# 16_MIPI_DSI_TX.net
KiCad netlist of a schematic drawn in Altium Designer
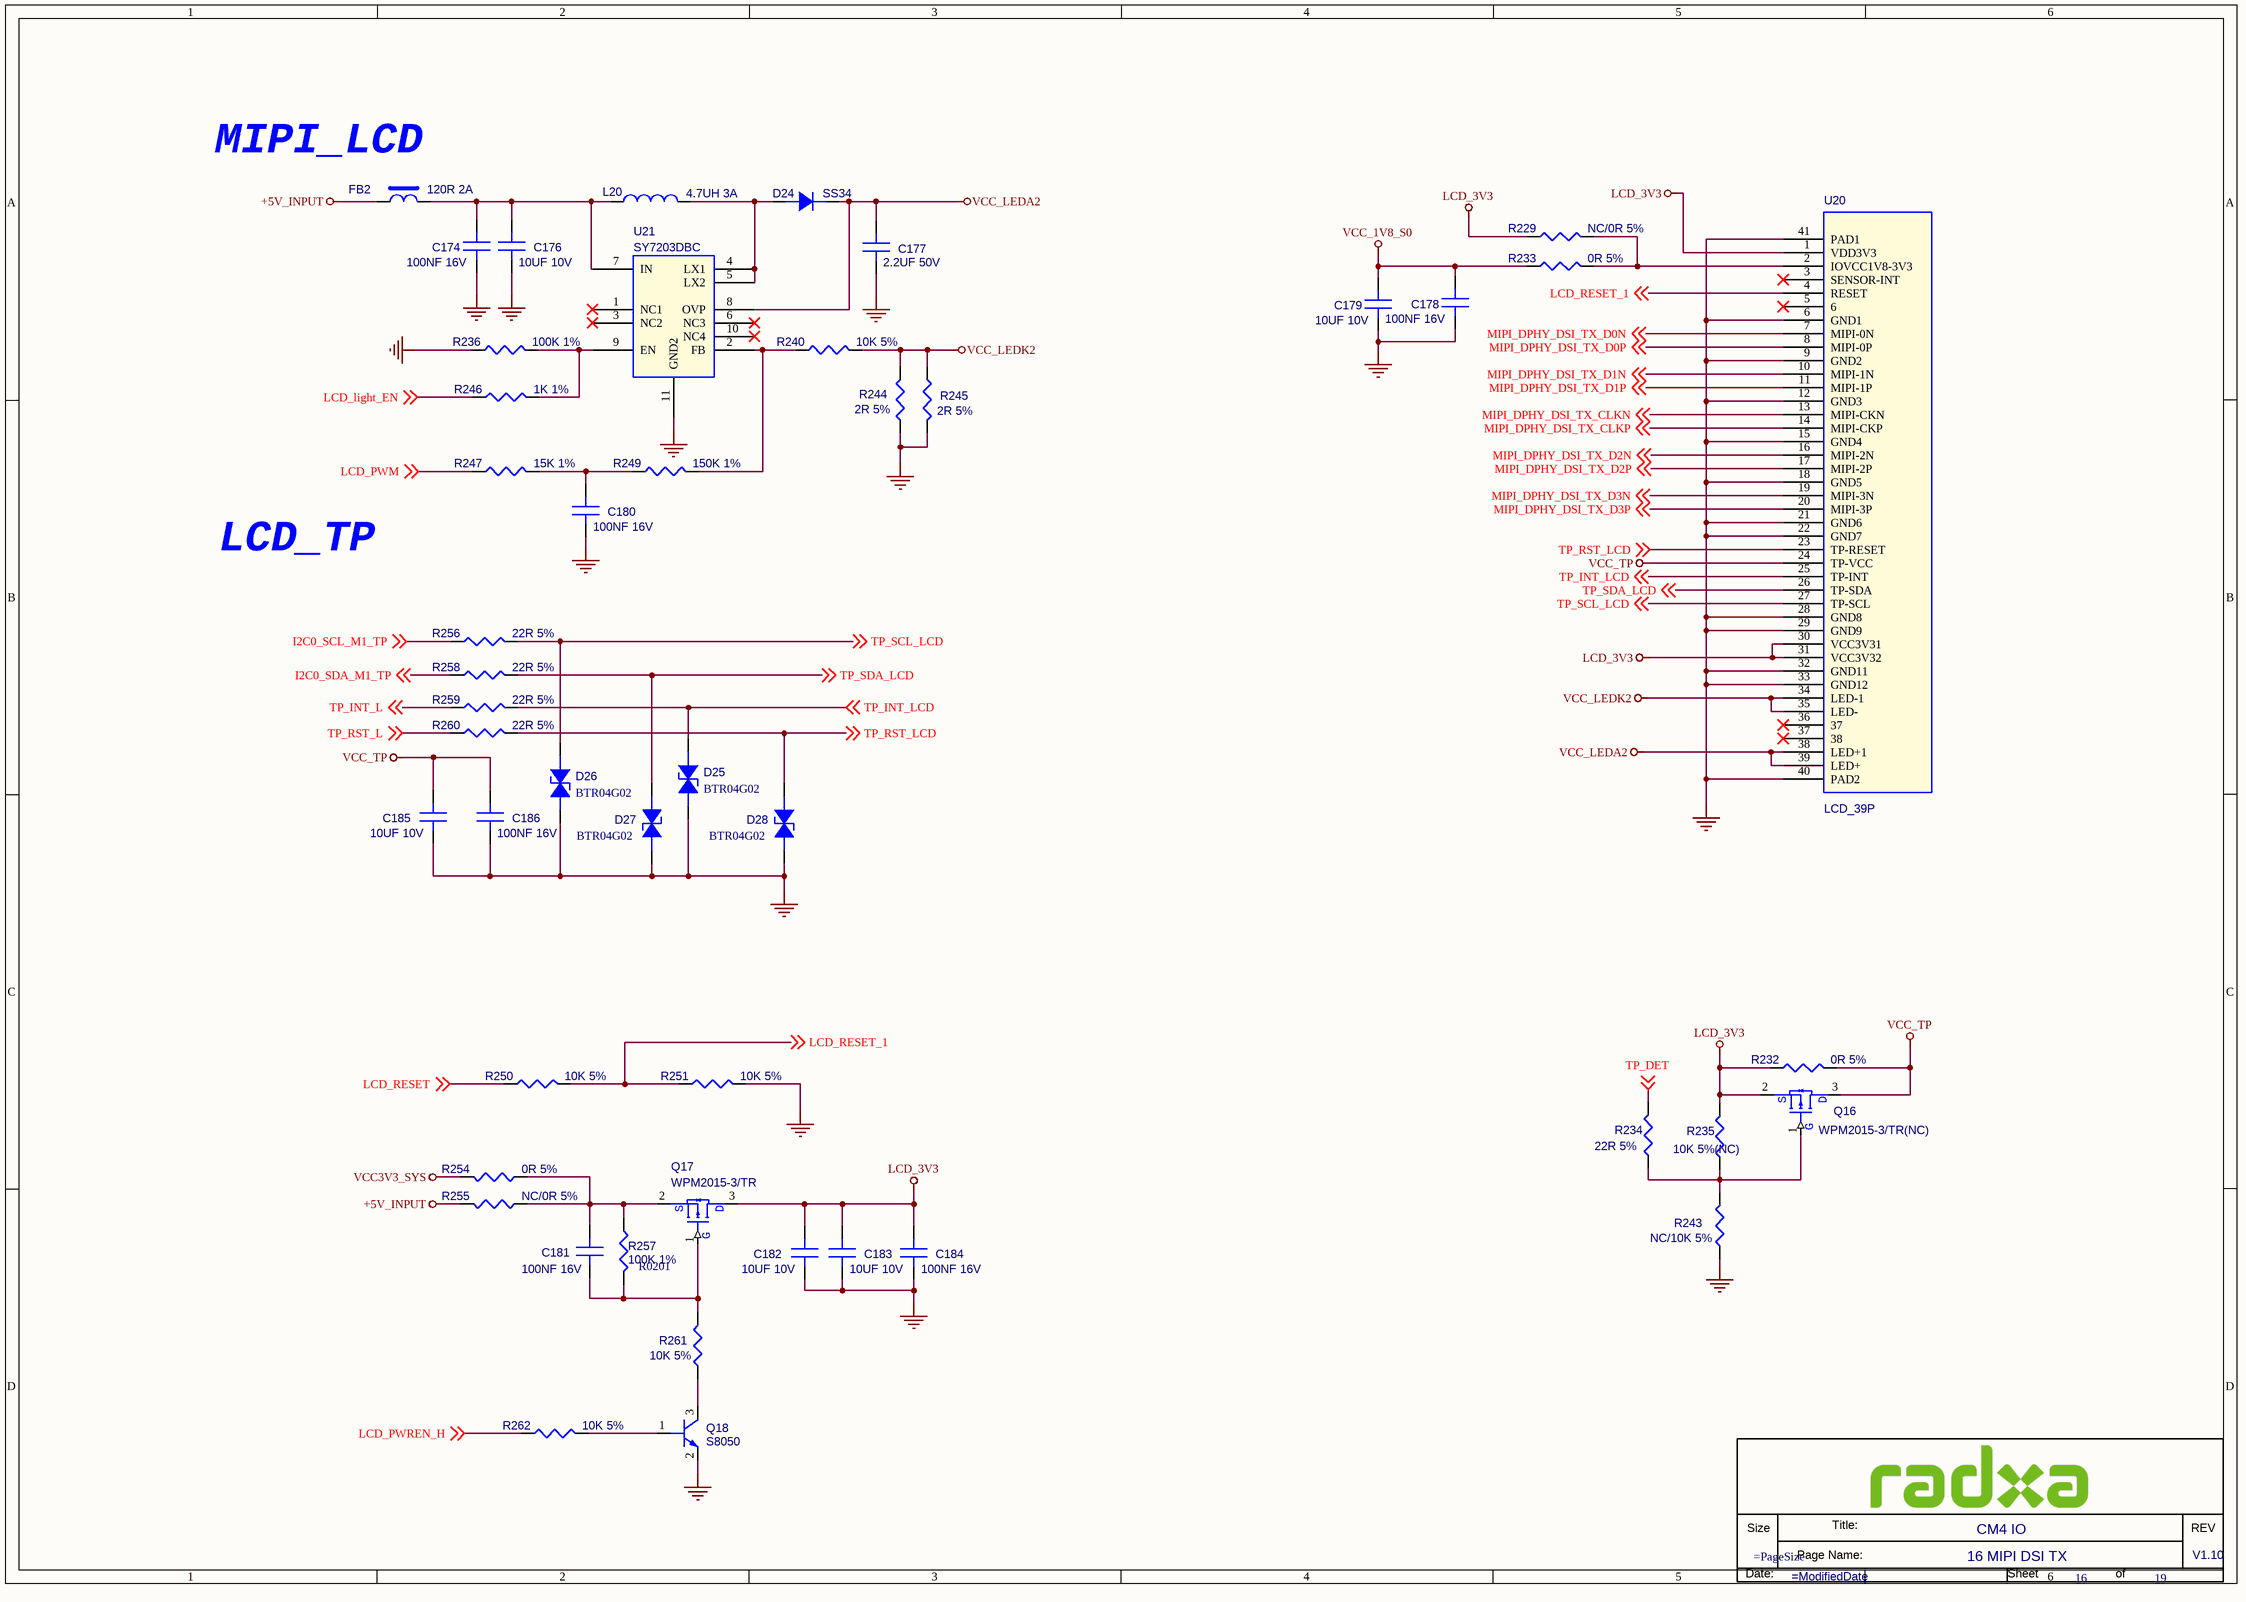
[diagram p0: 16 MIPI DSI TX.SchDoc]

(export (version "E")
  (design (tool "Eeschema 10.0.6"))
  (components
    (comp (ref "C174")
      (value "100NF 16V")
      (footprint "C0201")
      (description "SMD  0201  100NF  16V  X5R  ±20%  ROHS")
      (fields (field (name "PART NUMBER") "A1C01.00099"))
      (libsource (lib "*") (part "C"))
    )
    (comp (ref "C176")
      (value "10UF 10V")
      (footprint "C0603")
      (description "SMD  0603  10UF  10V  X5R  ±10%  ROHS")
      (fields (field (name "PART NUMBER") "A1C01.00270"))
      (libsource (lib "*") (part "C"))
    )
    (comp (ref "C177")
      (value "2.2UF 50V")
      (footprint "C0603")
      (description "SMD  0603  2.2UF  50V  X5R  ±10%  ROHS")
      (fields (field (name "PART NUMBER") "A1C01.00235"))
      (libsource (lib "*") (part "C"))
    )
    (comp (ref "C178")
      (value "100NF 16V")
      (footprint "C0201")
      (description "SMD  0201  100NF  16V  X5R  ±20%  ROHS")
      (fields (field (name "PART NUMBER") "A1C01.00099"))
      (libsource (lib "*") (part "C"))
    )
    (comp (ref "C179")
      (value "10UF 10V")
      (footprint "C0603")
      (description "SMD  0603  10UF  10V  X5R  ±10%  ROHS")
      (fields (field (name "PART NUMBER") "A1C01.00270"))
      (libsource (lib "*") (part "C"))
    )
    (comp (ref "C180")
      (value "100NF 16V")
      (footprint "C0201")
      (description "SMD  0201  100NF  16V  X5R  ±20%  ROHS")
      (fields (field (name "PART NUMBER") "A1C01.00099"))
      (libsource (lib "*") (part "C"))
    )
    (comp (ref "C181")
      (value "100NF 16V")
      (footprint "C0201")
      (description "SMD  0201  100NF  16V  X5R  ±20%  ROHS")
      (fields (field (name "PART NUMBER") "A1C01.00099"))
      (libsource (lib "*") (part "C"))
    )
    (comp (ref "C182")
      (value "10UF 10V")
      (footprint "C0603")
      (description "SMD  0603  10UF  10V  X5R  ±10%  ROHS")
      (fields (field (name "PART NUMBER") "A1C01.00270"))
      (libsource (lib "*") (part "C"))
    )
    (comp (ref "C183")
      (value "10UF 10V")
      (footprint "C0603")
      (description "SMD  0603  10UF  10V  X5R  ±10%  ROHS")
      (fields (field (name "PART NUMBER") "A1C01.00270"))
      (libsource (lib "*") (part "C"))
    )
    (comp (ref "C184")
      (value "100NF 16V")
      (footprint "C0201")
      (description "SMD  0201  100NF  16V  X5R  ±20%  ROHS")
      (fields (field (name "PART NUMBER") "A1C01.00099"))
      (libsource (lib "*") (part "C"))
    )
    (comp (ref "C185")
      (value "10UF 10V")
      (footprint "C0603")
      (description "SMD  0603  10UF  10V  X5R  ±10%  ROHS")
      (fields (field (name "PART NUMBER") "A1C01.00270"))
      (libsource (lib "*") (part "C"))
    )
    (comp (ref "C186")
      (value "100NF 16V")
      (footprint "C0201")
      (description "SMD  0201  100NF  16V  X5R  ±20%  ROHS")
      (fields (field (name "PART NUMBER") "A1C01.00099"))
      (libsource (lib "*") (part "C"))
    )
    (comp (ref "D24")
      (value "SS34")
      (footprint "DO_214AC")
      (description "SMD  编带  DO-214AC  SS34  CJ  ROHS")
      (fields (field (name "PART NUMBER") "A1D02.00052"))
      (libsource (lib "*") (part "DIODE"))
    )
    (comp (ref "D25")
      (value "BTR04G02")
      (footprint "DFN1006-2L")
      (description "SMD  编带  0402  BTR04G02  B-tron  ROHS")
      (fields (field (name "PART NUMBER") "A1D02.00002"))
      (libsource (lib "*") (part "ESD"))
    )
    (comp (ref "D26")
      (value "BTR04G02")
      (footprint "DFN1006-2L")
      (description "SMD  编带  0402  BTR04G02  B-tron  ROHS")
      (fields (field (name "PART NUMBER") "A1D02.00002"))
      (libsource (lib "*") (part "ESD"))
    )
    (comp (ref "D27")
      (value "BTR04G02")
      (footprint "DFN1006-2L")
      (description "SMD  编带  0402  BTR04G02  B-tron  ROHS")
      (fields (field (name "PART NUMBER") "A1D02.00002"))
      (libsource (lib "*") (part "ESD"))
    )
    (comp (ref "D28")
      (value "BTR04G02")
      (footprint "DFN1006-2L")
      (description "SMD  编带  0402  BTR04G02  B-tron  ROHS")
      (fields (field (name "PART NUMBER") "A1D02.00002"))
      (libsource (lib "*") (part "ESD"))
    )
    (comp (ref "FB2")
      (value "120R 2A")
      (footprint "FB0603")
      (description "SMD  0603  FB120R  2A  PZ1608U121-2R0TF  ±25%  Sunlord(顺络)  ROHS")
      (fields (field (name "PART NUMBER") "A1L09.00003"))
      (libsource (lib "*") (part "BEAD"))
    )
    (comp (ref "L20")
      (value "4.7UH 3A")
      (footprint "L_3015")
      (description "SMD  带屏蔽  3*3*1.5mm  4.7UH  3A  ±20%  RXWHJ3015-4R7MT  ROHS")
      (fields (field (name "PART NUMBER") "A1L01.00021"))
      (libsource (lib "*") (part "L"))
    )
    (comp (ref "Q16")
      (value "WPM2015-3/TR(NC)")
      (footprint "SOT_23")
      (description "SMD编带  SOT-23  WPM2015-3/TR  P沟道  ROHS")
      (fields (field (name "PART NUMBER") "A1D01.00019"))
      (libsource (lib "*") (part "MOSFET_PNP"))
    )
    (comp (ref "Q17")
      (value "WPM2015-3/TR")
      (footprint "SOT_23")
      (description "SMD编带  SOT-23  WPM2015-3/TR  P沟道  ROHS")
      (fields (field (name "PART NUMBER") "A1D01.00019"))
      (libsource (lib "*") (part "MOSFET_PNP"))
    )
    (comp (ref "Q18")
      (value "S8050")
      (footprint "SOT_23")
      (description "SMD编带  SOT-23  S8050  NPN  ROHS")
      (fields
        (field (name "PART NUMBER") "A1D01.00009")
        (field (name "MANUFACTURER") "长电")
        (field (name "CREATED BY") "JJJ")
      )
      (libsource (lib "*") (part "NPN"))
    )
    (comp (ref "R229")
      (value "NC/0R 5%")
      (footprint "R0402")
      (description "SMD  0201  0R  1/20W  ±5%  ROHS")
      (fields (field (name "PART NUMBER") "A1R01.00027"))
      (libsource (lib "*") (part "R"))
    )
    (comp (ref "R232")
      (value "0R 5%")
      (footprint "R0402")
      (description "SMD  0201  0R  1/20W  ±5%  ROHS")
      (fields (field (name "PART NUMBER") "A1R01.00027"))
      (libsource (lib "*") (part "R"))
    )
    (comp (ref "R233")
      (value "0R 5%")
      (footprint "R0402")
      (description "SMD  0201  0R  1/20W  ±5%  ROHS")
      (fields (field (name "PART NUMBER") "A1R01.00027"))
      (libsource (lib "*") (part "R"))
    )
    (comp (ref "R234")
      (value "22R 5%")
      (footprint "R0402")
      (description "SMD  0201  22R  1/20W  ±5%  ROHS")
      (fields (field (name "PART NUMBER") "A1R01.00024"))
      (libsource (lib "*") (part "R"))
    )
    (comp (ref "R235")
      (value "10K 5%(NC)")
      (footprint "R0402")
      (description "SMD  0201  10K  1/20W  ±5%  ROHS")
      (fields (field (name "PART NUMBER") "A1R01.00012"))
      (libsource (lib "*") (part "R"))
    )
    (comp (ref "R236")
      (value "100K 1%")
      (footprint "R0402")
      (description "SMD  0201  100K  1/20W  ±1%  ROHS")
      (fields (field (name "PART NUMBER") "A1R01.00165"))
      (libsource (lib "*") (part "R"))
    )
    (comp (ref "R240")
      (value "10K 5%")
      (footprint "R0402")
      (description "SMD  0201  10K  1/20W  ±5%  ROHS")
      (fields (field (name "PART NUMBER") "A1R01.00012"))
      (libsource (lib "*") (part "R"))
    )
    (comp (ref "R243")
      (value "NC/10K 5%")
      (footprint "R0402")
      (description "SMD  0201  10K  1/20W  ±5%  ROHS")
      (fields (field (name "PART NUMBER") "A1R01.00012"))
      (libsource (lib "*") (part "R"))
    )
    (comp (ref "R244")
      (value "2R 5%")
      (footprint "R0402")
      (description "SMD  0603  2R  1/10W  ±5%  ROHS")
      (fields (field (name "PART NUMBER") "A1R01.00329"))
      (libsource (lib "*") (part "R"))
    )
    (comp (ref "R245")
      (value "2R 5%")
      (footprint "R0402")
      (description "SMD  0603  2R  1/10W  ±5%  ROHS")
      (fields (field (name "PART NUMBER") "A1R01.00329"))
      (libsource (lib "*") (part "R"))
    )
    (comp (ref "R246")
      (value "1K 1%")
      (footprint "R0402")
      (description "SMD  0201  1K  1/20W  ±1%  ROHS")
      (fields (field (name "PART NUMBER") "A1R01.00111"))
      (libsource (lib "*") (part "R"))
    )
    (comp (ref "R247")
      (value "15K 1%")
      (footprint "R0402")
      (description "SMD  0201  15K  1/20W  ±1%  ROHS")
      (fields (field (name "PART NUMBER") "A1R01.00119"))
      (libsource (lib "*") (part "R"))
    )
    (comp (ref "R249")
      (value "150K 1%")
      (footprint "R0402")
      (description "SMD  0201  150K  1/20W  ±1%  ROHS")
      (fields (field (name "PART NUMBER") "A1R01.00095"))
      (libsource (lib "*") (part "R"))
    )
    (comp (ref "R250")
      (value "10K 5%")
      (footprint "R0402")
      (description "SMD  0201  10K  1/20W  ±5%  ROHS")
      (fields (field (name "PART NUMBER") "A1R01.00012"))
      (libsource (lib "*") (part "R"))
    )
    (comp (ref "R251")
      (value "10K 5%")
      (footprint "R0402")
      (description "SMD  0201  10K  1/20W  ±5%  ROHS")
      (fields (field (name "PART NUMBER") "A1R01.00012"))
      (libsource (lib "*") (part "R"))
    )
    (comp (ref "R254")
      (value "0R 5%")
      (footprint "R0402")
      (description "SMD  0402  0R  1/16W  ±5%  ROHS")
      (fields (field (name "PART NUMBER") "A1R01.00030"))
      (libsource (lib "*") (part "R"))
    )
    (comp (ref "R255")
      (value "NC/0R 5%")
      (footprint "R0402")
      (description "SMD  0201  0R  1/20W  ±5%  ROHS")
      (fields (field (name "PART NUMBER") "A1R01.00027"))
      (libsource (lib "*") (part "R"))
    )
    (comp (ref "R256")
      (value "22R 5%")
      (footprint "R0402")
      (description "SMD  0201  22R  1/20W  ±5%  ROHS")
      (fields (field (name "PART NUMBER") "A1R01.00024"))
      (libsource (lib "*") (part "R"))
    )
    (comp (ref "R257")
      (value "100K 1%")
      (footprint "R0402")
      (description "SMD  0201  100K  1/20W  ±1%  ROHS")
      (fields (field (name "PCB FOOTPRINT") "R0201") (field (name "PART NUMBER") "A1R01.00165"))
      (libsource (lib "*") (part "R"))
    )
    (comp (ref "R258")
      (value "22R 5%")
      (footprint "R0402")
      (description "SMD  0201  22R  1/20W  ±5%  ROHS")
      (fields (field (name "PART NUMBER") "A1R01.00024"))
      (libsource (lib "*") (part "R"))
    )
    (comp (ref "R259")
      (value "22R 5%")
      (footprint "R0402")
      (description "SMD  0201  22R  1/20W  ±5%  ROHS")
      (fields (field (name "PART NUMBER") "A1R01.00024"))
      (libsource (lib "*") (part "R"))
    )
    (comp (ref "R260")
      (value "22R 5%")
      (footprint "R0402")
      (description "SMD  0201  22R  1/20W  ±5%  ROHS")
      (fields (field (name "PART NUMBER") "A1R01.00024"))
      (libsource (lib "*") (part "R"))
    )
    (comp (ref "R261")
      (value "10K 5%")
      (footprint "R0402")
      (description "SMD  0201  10K  1/20W  ±5%  ROHS")
      (fields (field (name "PART NUMBER") "A1R01.00012"))
      (libsource (lib "*") (part "R"))
    )
    (comp (ref "R262")
      (value "10K 5%")
      (footprint "R0402")
      (description "SMD  0201  10K  1/20W  ±5%  ROHS")
      (fields (field (name "PART NUMBER") "A1R01.00012"))
      (libsource (lib "*") (part "R"))
    )
    (comp (ref "U20")
      (value "LCD_39P")
      (footprint "FPC_39P_0D3_LIE")
      (description "SMD  下接触  卧式  39PIN  0.3mm脚距  后翻盖H1.0  FH35C-39S-0.3SHW(50)  镀金  广濑  ROHS")
      (fields (field (name "PART NUMBER") "A1J06.00001"))
      (libsource (lib "*") (part "LCD_39P"))
    )
    (comp (ref "U21")
      (value "SY7203DBC")
      (footprint "DFN10_0D5_3")
      (description "SMD  升压  SY7203DBC  DFN3X3-10  silergy(矽力杰)  ROHS")
      (fields (field (name "PART NUMBER") "A1I01.00260"))
      (libsource (lib "*") (part "SY7203DBC"))
    )
  )
  (nets
    (net (code "1") (name "+5V_INPUT") (class "Default")
      (node (ref "FB2") (pin "1") (pinfunction "1_1") (pintype "passive"))
      (node (ref "R255") (pin "1") (pinfunction "1_1") (pintype "passive"))
    )
    (net (code "2") (name "GND") (class "Default")
      (node (ref "C174") (pin "2") (pinfunction "B_2") (pintype "passive"))
      (node (ref "C176") (pin "2") (pinfunction "B_2") (pintype "passive"))
      (node (ref "C177") (pin "2") (pinfunction "B_2") (pintype "passive"))
      (node (ref "C178") (pin "2") (pinfunction "B_2") (pintype "passive"))
      (node (ref "C179") (pin "2") (pinfunction "B_2") (pintype "passive"))
      (node (ref "C180") (pin "1") (pinfunction "A_1") (pintype "passive"))
      (node (ref "C182") (pin "2") (pinfunction "B_2") (pintype "passive"))
      (node (ref "C183") (pin "2") (pinfunction "B_2") (pintype "passive"))
      (node (ref "C184") (pin "2") (pinfunction "B_2") (pintype "passive"))
      (node (ref "C185") (pin "2") (pinfunction "B_2") (pintype "passive"))
      (node (ref "C186") (pin "2") (pinfunction "B_2") (pintype "passive"))
      (node (ref "D25") (pin "2") (pinfunction "CATHODE_2") (pintype "passive"))
      (node (ref "D26") (pin "2") (pinfunction "CATHODE_2") (pintype "passive"))
      (node (ref "D27") (pin "2") (pinfunction "CATHODE_2") (pintype "passive"))
      (node (ref "D28") (pin "2") (pinfunction "CATHODE_2") (pintype "passive"))
      (node (ref "Q18") (pin "2") (pinfunction "EMITTER_2") (pintype "passive"))
      (node (ref "R236") (pin "1") (pinfunction "1_1") (pintype "passive"))
      (node (ref "R243") (pin "1") (pinfunction "1_1") (pintype "passive"))
      (node (ref "R244") (pin "2") (pinfunction "2_2") (pintype "passive"))
      (node (ref "R245") (pin "2") (pinfunction "2_2") (pintype "passive"))
      (node (ref "R251") (pin "2") (pinfunction "2_2") (pintype "passive"))
      (node (ref "U20") (pin "12") (pinfunction "GND3_12") (pintype "passive"))
      (node (ref "U20") (pin "15") (pinfunction "GND4_15") (pintype "passive"))
      (node (ref "U20") (pin "18") (pinfunction "GND5_18") (pintype "passive"))
      (node (ref "U20") (pin "21") (pinfunction "GND6_21") (pintype "passive"))
      (node (ref "U20") (pin "22") (pinfunction "GND7_22") (pintype "passive"))
      (node (ref "U20") (pin "28") (pinfunction "GND8_28") (pintype "passive"))
      (node (ref "U20") (pin "29") (pinfunction "GND9_29") (pintype "passive"))
      (node (ref "U20") (pin "32") (pinfunction "GND11_32") (pintype "passive"))
      (node (ref "U20") (pin "33") (pinfunction "GND12_33") (pintype "passive"))
      (node (ref "U20") (pin "40") (pinfunction "PAD2_40") (pintype "passive"))
      (node (ref "U20") (pin "41") (pinfunction "PAD1_41") (pintype "passive"))
      (node (ref "U20") (pin "6") (pinfunction "GND1_6") (pintype "passive"))
      (node (ref "U20") (pin "9") (pinfunction "GND2_9") (pintype "passive"))
      (node (ref "U21") (pin "11") (pinfunction "GND2_11") (pintype "passive"))
    )
    (net (code "3") (name "I2C0_SCL_M1_TP") (class "Default")
      (node (ref "R256") (pin "1") (pinfunction "1_1") (pintype "passive"))
    )
    (net (code "4") (name "I2C0_SDA_M1_TP") (class "Default")
      (node (ref "R258") (pin "1") (pinfunction "1_1") (pintype "passive"))
    )
    (net (code "5") (name "LCD_3V3") (class "Default")
      (node (ref "C182") (pin "1") (pinfunction "A_1") (pintype "passive"))
      (node (ref "C183") (pin "1") (pinfunction "A_1") (pintype "passive"))
      (node (ref "C184") (pin "1") (pinfunction "A_1") (pintype "passive"))
      (node (ref "Q16") (pin "2") (pinfunction "S_2") (pintype "passive"))
      (node (ref "Q17") (pin "3") (pinfunction "D_3") (pintype "passive"))
      (node (ref "R229") (pin "1") (pinfunction "1_1") (pintype "passive"))
      (node (ref "R232") (pin "1") (pinfunction "1_1") (pintype "passive"))
      (node (ref "R235") (pin "2") (pinfunction "2_2") (pintype "passive"))
      (node (ref "U20") (pin "1") (pinfunction "VDD3V3_1") (pintype "passive"))
      (node (ref "U20") (pin "30") (pinfunction "VCC3V31_30") (pintype "passive"))
      (node (ref "U20") (pin "31") (pinfunction "VCC3V32_31") (pintype "passive"))
    )
    (net (code "6") (name "LCD_PWM") (class "Default")
      (node (ref "R247") (pin "1") (pinfunction "1_1") (pintype "passive"))
    )
    (net (code "7") (name "LCD_PWREN_H") (class "Default")
      (node (ref "R262") (pin "1") (pinfunction "1_1") (pintype "passive"))
    )
    (net (code "8") (name "LCD_RESET") (class "Default")
      (node (ref "R250") (pin "1") (pinfunction "1_1") (pintype "passive"))
    )
    (net (code "9") (name "LCD_RESET_1") (class "Default")
      (node (ref "R250") (pin "2") (pinfunction "2_2") (pintype "passive"))
      (node (ref "R251") (pin "1") (pinfunction "1_1") (pintype "passive"))
      (node (ref "U20") (pin "4") (pinfunction "RESET_4") (pintype "passive"))
    )
    (net (code "10") (name "LCD_light_EN") (class "Default")
      (node (ref "R246") (pin "1") (pinfunction "1_1") (pintype "passive"))
    )
    (net (code "11") (name "MIPI_DPHY_DSI_TX_CLKN") (class "Default")
      (node (ref "U20") (pin "13") (pinfunction "MIPI-CKN_13") (pintype "passive"))
    )
    (net (code "12") (name "MIPI_DPHY_DSI_TX_CLKP") (class "Default")
      (node (ref "U20") (pin "14") (pinfunction "MIPI-CKP_14") (pintype "passive"))
    )
    (net (code "13") (name "MIPI_DPHY_DSI_TX_D0N") (class "Default")
      (node (ref "U20") (pin "7") (pinfunction "MIPI-0N_7") (pintype "passive"))
    )
    (net (code "14") (name "MIPI_DPHY_DSI_TX_D0P") (class "Default")
      (node (ref "U20") (pin "8") (pinfunction "MIPI-0P_8") (pintype "passive"))
    )
    (net (code "15") (name "MIPI_DPHY_DSI_TX_D1N") (class "Default")
      (node (ref "U20") (pin "10") (pinfunction "MIPI-1N_10") (pintype "passive"))
    )
    (net (code "16") (name "MIPI_DPHY_DSI_TX_D1P") (class "Default")
      (node (ref "U20") (pin "11") (pinfunction "MIPI-1P_11") (pintype "passive"))
    )
    (net (code "17") (name "MIPI_DPHY_DSI_TX_D2N") (class "Default")
      (node (ref "U20") (pin "16") (pinfunction "MIPI-2N_16") (pintype "passive"))
    )
    (net (code "18") (name "MIPI_DPHY_DSI_TX_D2P") (class "Default")
      (node (ref "U20") (pin "17") (pinfunction "MIPI-2P_17") (pintype "passive"))
    )
    (net (code "19") (name "MIPI_DPHY_DSI_TX_D3N") (class "Default")
      (node (ref "U20") (pin "19") (pinfunction "MIPI-3N_19") (pintype "passive"))
    )
    (net (code "20") (name "MIPI_DPHY_DSI_TX_D3P") (class "Default")
      (node (ref "U20") (pin "20") (pinfunction "MIPI-3P_20") (pintype "passive"))
    )
    (net (code "21") (name "Net-(C174-A)") (class "Default")
      (node (ref "C174") (pin "1") (pinfunction "A_1") (pintype "passive"))
      (node (ref "C176") (pin "1") (pinfunction "A_1") (pintype "passive"))
      (node (ref "FB2") (pin "2") (pinfunction "2_2") (pintype "passive"))
      (node (ref "L20") (pin "1") (pinfunction "1_1") (pintype "passive"))
      (node (ref "U21") (pin "7") (pinfunction "IN_7") (pintype "passive"))
    )
    (net (code "22") (name "Net-(C180-B)") (class "Default")
      (node (ref "C180") (pin "2") (pinfunction "B_2") (pintype "passive"))
      (node (ref "R247") (pin "2") (pinfunction "2_2") (pintype "passive"))
      (node (ref "R249") (pin "1") (pinfunction "1_1") (pintype "passive"))
    )
    (net (code "23") (name "Net-(C181-A)") (class "Default")
      (node (ref "C181") (pin "1") (pinfunction "A_1") (pintype "passive"))
      (node (ref "Q17") (pin "2") (pinfunction "S_2") (pintype "passive"))
      (node (ref "R254") (pin "2") (pinfunction "2_2") (pintype "passive"))
      (node (ref "R255") (pin "2") (pinfunction "2_2") (pintype "passive"))
      (node (ref "R257") (pin "1") (pinfunction "1_1") (pintype "passive"))
    )
    (net (code "24") (name "Net-(C181-B)") (class "Default")
      (node (ref "C181") (pin "2") (pinfunction "B_2") (pintype "passive"))
      (node (ref "Q17") (pin "1") (pinfunction "G_1") (pintype "input"))
      (node (ref "R257") (pin "2") (pinfunction "2_2") (pintype "passive"))
      (node (ref "R261") (pin "1") (pinfunction "1_1") (pintype "passive"))
    )
    (net (code "25") (name "Net-(D24-A)") (class "Default")
      (node (ref "D24") (pin "1") (pinfunction "A_1") (pintype "passive"))
      (node (ref "L20") (pin "2") (pinfunction "2_2") (pintype "passive"))
      (node (ref "U21") (pin "4") (pinfunction "LX1_4") (pintype "passive"))
      (node (ref "U21") (pin "5") (pinfunction "LX2_5") (pintype "passive"))
    )
    (net (code "26") (name "Net-(Q16-G)") (class "Default")
      (node (ref "Q16") (pin "1") (pinfunction "G_1") (pintype "input"))
      (node (ref "R234") (pin "2") (pinfunction "2_2") (pintype "passive"))
      (node (ref "R235") (pin "1") (pinfunction "1_1") (pintype "passive"))
      (node (ref "R243") (pin "2") (pinfunction "2_2") (pintype "passive"))
    )
    (net (code "27") (name "Net-(Q18-BASE)") (class "Default")
      (node (ref "Q18") (pin "1") (pinfunction "BASE_1") (pintype "passive"))
      (node (ref "R262") (pin "2") (pinfunction "2_2") (pintype "passive"))
    )
    (net (code "28") (name "Net-(Q18-COLLECTOR)") (class "Default")
      (node (ref "Q18") (pin "3") (pinfunction "COLLECTOR_3") (pintype "passive"))
      (node (ref "R261") (pin "2") (pinfunction "2_2") (pintype "passive"))
    )
    (net (code "29") (name "Net-(U20-IOVCC1V8-3V3)") (class "Default")
      (node (ref "R229") (pin "2") (pinfunction "2_2") (pintype "passive"))
      (node (ref "R233") (pin "2") (pinfunction "2_2") (pintype "passive"))
      (node (ref "U20") (pin "2") (pinfunction "IOVCC1V8-3V3_2") (pintype "passive"))
    )
    (net (code "30") (name "Net-(U21-EN)") (class "Default")
      (node (ref "R236") (pin "2") (pinfunction "2_2") (pintype "passive"))
      (node (ref "R246") (pin "2") (pinfunction "2_2") (pintype "passive"))
      (node (ref "U21") (pin "9") (pinfunction "EN_9") (pintype "passive"))
    )
    (net (code "31") (name "Net-(U21-FB)") (class "Default")
      (node (ref "R240") (pin "1") (pinfunction "1_1") (pintype "passive"))
      (node (ref "R249") (pin "2") (pinfunction "2_2") (pintype "passive"))
      (node (ref "U21") (pin "2") (pinfunction "FB_2") (pintype "passive"))
    )
    (net (code "32") (name "TP_DET") (class "Default")
      (node (ref "R234") (pin "1") (pinfunction "1_1") (pintype "passive"))
    )
    (net (code "33") (name "TP_INT_L") (class "Default")
      (node (ref "R259") (pin "1") (pinfunction "1_1") (pintype "passive"))
    )
    (net (code "34") (name "TP_INT_LCD") (class "Default")
      (node (ref "D25") (pin "1") (pinfunction "ANODE_1") (pintype "passive"))
      (node (ref "R259") (pin "2") (pinfunction "2_2") (pintype "passive"))
      (node (ref "U20") (pin "25") (pinfunction "TP-INT_25") (pintype "passive"))
    )
    (net (code "35") (name "TP_RST_L") (class "Default")
      (node (ref "R260") (pin "1") (pinfunction "1_1") (pintype "passive"))
    )
    (net (code "36") (name "TP_RST_LCD") (class "Default")
      (node (ref "D28") (pin "1") (pinfunction "ANODE_1") (pintype "passive"))
      (node (ref "R260") (pin "2") (pinfunction "2_2") (pintype "passive"))
      (node (ref "U20") (pin "23") (pinfunction "TP-RESET_23") (pintype "passive"))
    )
    (net (code "37") (name "TP_SCL_LCD") (class "Default")
      (node (ref "D26") (pin "1") (pinfunction "ANODE_1") (pintype "passive"))
      (node (ref "R256") (pin "2") (pinfunction "2_2") (pintype "passive"))
      (node (ref "U20") (pin "27") (pinfunction "TP-SCL_27") (pintype "passive"))
    )
    (net (code "38") (name "TP_SDA_LCD") (class "Default")
      (node (ref "D27") (pin "1") (pinfunction "ANODE_1") (pintype "passive"))
      (node (ref "R258") (pin "2") (pinfunction "2_2") (pintype "passive"))
      (node (ref "U20") (pin "26") (pinfunction "TP-SDA_26") (pintype "passive"))
    )
    (net (code "39") (name "VCC3V3_SYS") (class "Default")
      (node (ref "R254") (pin "1") (pinfunction "1_1") (pintype "passive"))
    )
    (net (code "40") (name "VCC_1V8_S0") (class "Default")
      (node (ref "C178") (pin "1") (pinfunction "A_1") (pintype "passive"))
      (node (ref "C179") (pin "1") (pinfunction "A_1") (pintype "passive"))
      (node (ref "R233") (pin "1") (pinfunction "1_1") (pintype "passive"))
    )
    (net (code "41") (name "VCC_LEDA2") (class "Default")
      (node (ref "C177") (pin "1") (pinfunction "A_1") (pintype "passive"))
      (node (ref "D24") (pin "2") (pinfunction "K_2") (pintype "passive"))
      (node (ref "U20") (pin "38") (pinfunction "LED+1_38") (pintype "passive"))
      (node (ref "U20") (pin "39") (pinfunction "LED+_39") (pintype "passive"))
      (node (ref "U21") (pin "8") (pinfunction "OVP_8") (pintype "passive"))
    )
    (net (code "42") (name "VCC_LEDK2") (class "Default")
      (node (ref "R240") (pin "2") (pinfunction "2_2") (pintype "passive"))
      (node (ref "R244") (pin "1") (pinfunction "1_1") (pintype "passive"))
      (node (ref "R245") (pin "1") (pinfunction "1_1") (pintype "passive"))
      (node (ref "U20") (pin "34") (pinfunction "LED-1_34") (pintype "passive"))
      (node (ref "U20") (pin "35") (pinfunction "LED-_35") (pintype "passive"))
    )
    (net (code "43") (name "VCC_TP") (class "Default")
      (node (ref "C185") (pin "1") (pinfunction "A_1") (pintype "passive"))
      (node (ref "C186") (pin "1") (pinfunction "A_1") (pintype "passive"))
      (node (ref "Q16") (pin "3") (pinfunction "D_3") (pintype "passive"))
      (node (ref "R232") (pin "2") (pinfunction "2_2") (pintype "passive"))
      (node (ref "U20") (pin "24") (pinfunction "TP-VCC_24") (pintype "passive"))
    )
    (net (code "44") (name "unconnected-(U20-6-Pad5)") (class "Default")
      (node (ref "U20") (pin "5") (pinfunction "6_5") (pintype "passive+no_connect"))
    )
    (net (code "45") (name "unconnected-(U20-37-Pad36)") (class "Default")
      (node (ref "U20") (pin "36") (pinfunction "37_36") (pintype "passive+no_connect"))
    )
    (net (code "46") (name "unconnected-(U20-38-Pad37)") (class "Default")
      (node (ref "U20") (pin "37") (pinfunction "38_37") (pintype "passive+no_connect"))
    )
    (net (code "47") (name "unconnected-(U20-SENSOR-INT-Pad3)") (class "Default")
      (node (ref "U20") (pin "3") (pinfunction "SENSOR-INT_3") (pintype "passive+no_connect"))
    )
    (net (code "48") (name "unconnected-(U21-NC1-Pad1)") (class "Default")
      (node (ref "U21") (pin "1") (pinfunction "NC1_1") (pintype "passive+no_connect"))
    )
    (net (code "49") (name "unconnected-(U21-NC2-Pad3)") (class "Default")
      (node (ref "U21") (pin "3") (pinfunction "NC2_3") (pintype "passive+no_connect"))
    )
    (net (code "50") (name "unconnected-(U21-NC3-Pad6)") (class "Default")
      (node (ref "U21") (pin "6") (pinfunction "NC3_6") (pintype "passive+no_connect"))
    )
    (net (code "51") (name "unconnected-(U21-NC4-Pad10)") (class "Default")
      (node (ref "U21") (pin "10") (pinfunction "NC4_10") (pintype "passive+no_connect"))
    )
  )
)
